# RC_motor_driver.net
KiCad netlist of a schematic drawn in Altium Designer
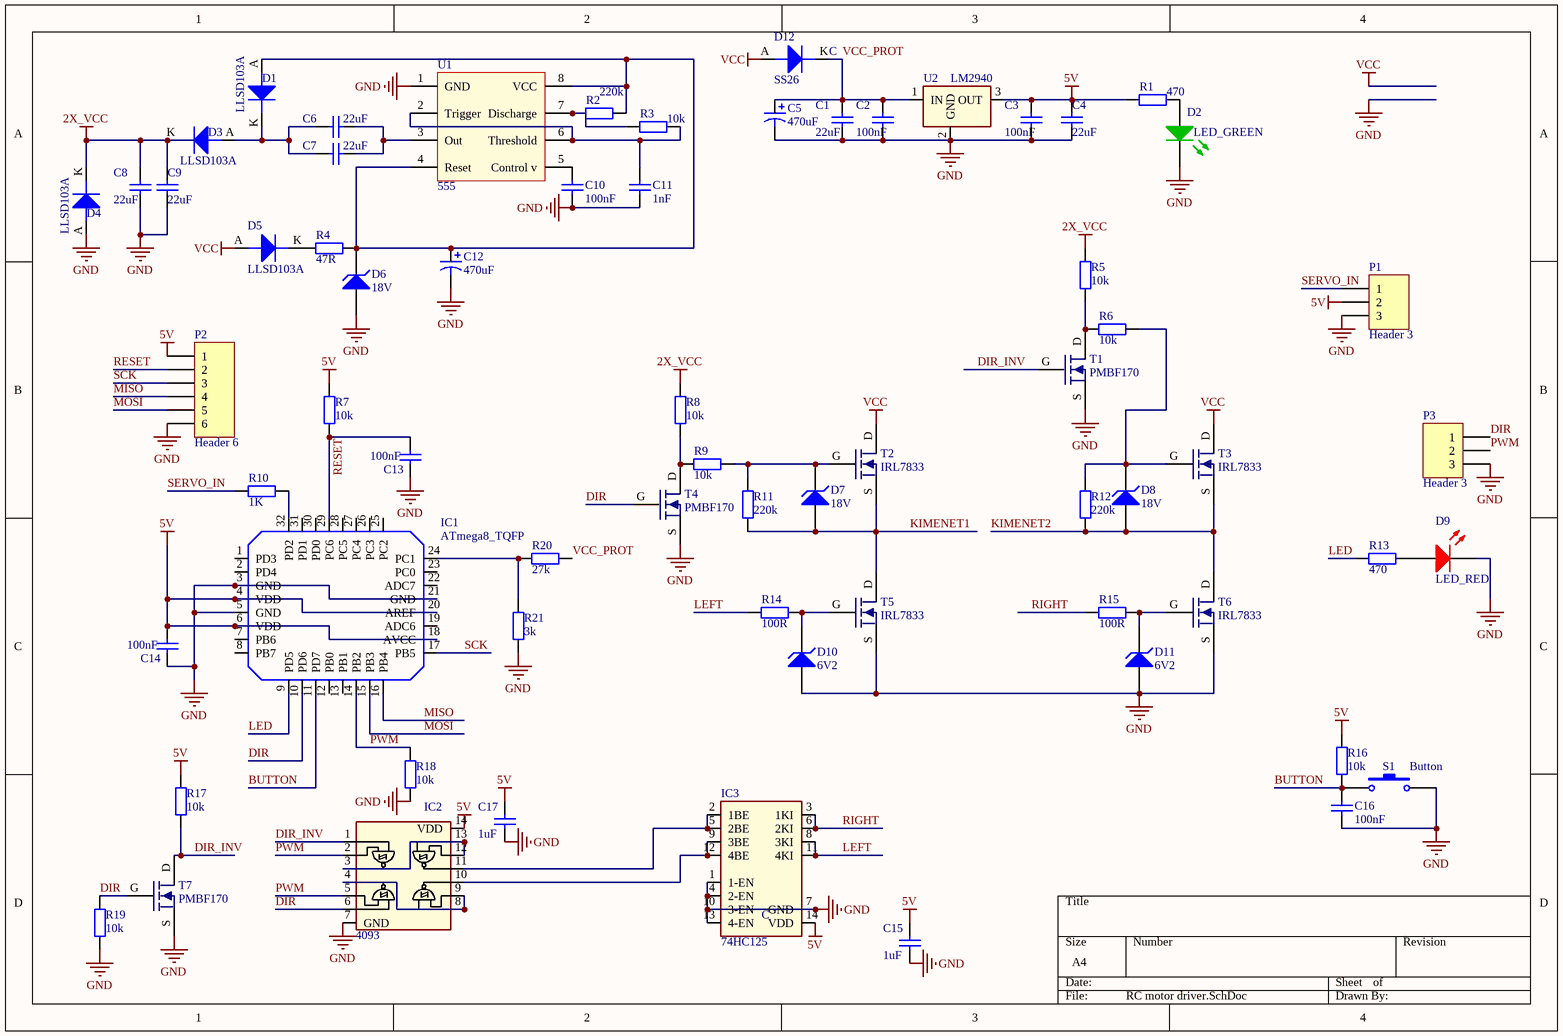
[diagram p0: RC motor driver.SchDoc]

(export (version "E")
  (design (tool "Eeschema 10.0.6"))
  (components
    (comp (ref "C1")
      (value "22uF")
      (footprint "FP_1210_CAP_N")
      (description "Capacitor")
      (libsource (lib "Capacitor") (part "CAP"))
    )
    (comp (ref "C2")
      (value "100nF")
      (footprint "FP_0805_CAP_085")
      (description "Capacitor")
      (libsource (lib "Capacitor") (part "CAP"))
    )
    (comp (ref "C3")
      (value "100nF")
      (footprint "FP_0805_CAP_085")
      (description "Capacitor")
      (libsource (lib "Capacitor") (part "CAP"))
    )
    (comp (ref "C4")
      (value "22uF")
      (footprint "FP_1210_CAP_N")
      (description "Capacitor")
      (libsource (lib "Capacitor") (part "CAP"))
    )
    (comp (ref "C5")
      (value "470uF")
      (footprint "cap_10x12")
      (description "Polarized Capacitor")
      (libsource (lib "Capacitor") (part "CAP_ELECT"))
    )
    (comp (ref "C6")
      (value "22uF")
      (footprint "FP_1210_CAP_N")
      (description "Capacitor")
      (libsource (lib "Capacitor") (part "CAP"))
    )
    (comp (ref "C7")
      (value "22uF")
      (footprint "FP_1210_CAP_N")
      (description "Capacitor")
      (libsource (lib "Capacitor") (part "CAP"))
    )
    (comp (ref "C8")
      (value "22uF")
      (footprint "FP_1210_CAP_N")
      (description "Capacitor")
      (libsource (lib "Capacitor") (part "CAP"))
    )
    (comp (ref "C9")
      (value "22uF")
      (footprint "FP_1210_CAP_N")
      (description "Capacitor")
      (libsource (lib "Capacitor") (part "CAP"))
    )
    (comp (ref "C10")
      (value "100nF")
      (footprint "FP_0805_CAP_085")
      (description "Capacitor")
      (libsource (lib "Capacitor") (part "CAP"))
    )
    (comp (ref "C11")
      (value "1nF")
      (footprint "FP_0805_CAP_085")
      (description "Capacitor")
      (libsource (lib "Capacitor") (part "CAP"))
    )
    (comp (ref "C12")
      (value "470uF")
      (footprint "cap_10x12")
      (description "Polarized Capacitor")
      (libsource (lib "Capacitor") (part "CAP_ELECT"))
    )
    (comp (ref "C13")
      (value "100nF")
      (footprint "FP_0805_CAP_085")
      (description "Capacitor")
      (libsource (lib "Capacitor") (part "CAP"))
    )
    (comp (ref "C14")
      (value "100nF")
      (footprint "FP_0805_CAP_085")
      (description "Capacitor")
      (libsource (lib "Capacitor") (part "CAP"))
    )
    (comp (ref "C15")
      (value "1uF")
      (footprint "FP_0805_CAP_085")
      (description "Capacitor")
      (libsource (lib "Capacitor") (part "CAP"))
    )
    (comp (ref "C16")
      (value "100nF")
      (footprint "FP_0805_CAP_085")
      (description "Capacitor")
      (libsource (lib "Capacitor") (part "CAP"))
    )
    (comp (ref "C17")
      (value "1uF")
      (footprint "FP_0805_CAP_085")
      (description "Capacitor")
      (libsource (lib "Capacitor") (part "CAP"))
    )
    (comp (ref "D1") (value "LLSD103A") (footprint "SOD-80") (libsource (lib "Diode") (part "DIODE_big")))
    (comp (ref "D2")
      (value "LED_GREEN")
      (footprint "FP_0805_LED_GREEN")
      (description "Typical LED")
      (libsource (lib "Led_optical") (part "LED_G"))
    )
    (comp (ref "D3") (value "LLSD103A") (footprint "SOD-80") (libsource (lib "Diode") (part "DIODE_big")))
    (comp (ref "D4") (value "LLSD103A") (footprint "SOD-80") (libsource (lib "Diode") (part "DIODE_big")))
    (comp (ref "D5") (value "LLSD103A") (footprint "SOD-80") (libsource (lib "Diode") (part "DIODE_big")))
    (comp (ref "D6")
      (value "18V")
      (footprint "SOD-80")
      (description "Zener Diode")
      (libsource (lib "Diode") (part "ZENER"))
    )
    (comp (ref "D7")
      (value "18V")
      (footprint "SOD-80")
      (description "Zener Diode")
      (libsource (lib "Diode") (part "ZENER"))
    )
    (comp (ref "D8")
      (value "18V")
      (footprint "SOD-80")
      (description "Zener Diode")
      (libsource (lib "Diode") (part "ZENER"))
    )
    (comp (ref "D9")
      (value "LED_RED")
      (footprint "FP_0805_LED_RED")
      (description "Typical LED")
      (libsource (lib "Led_optical") (part "LED_R"))
    )
    (comp (ref "D10")
      (value "6V2")
      (footprint "SOD-80")
      (description "Zener Diode")
      (libsource (lib "Diode") (part "ZENER"))
    )
    (comp (ref "D11")
      (value "6V2")
      (footprint "SOD-80")
      (description "Zener Diode")
      (libsource (lib "Diode") (part "ZENER"))
    )
    (comp (ref "D12") (value "SS26") (footprint "subsma") (libsource (lib "Diode") (part "DIODE_big")))
    (comp (ref "IC1")
      (value "ATmega8_TQFP")
      (footprint "TQFP32_N")
      (libsource (lib "uC") (part "ATmega8_TQFP"))
    )
    (comp (ref "IC2")
      (value "4093")
      (footprint "Gate_SOIC14")
      (description "Quad 2-Input NAND Schmitt Trigger")
      (libsource (lib "Logic_gate") (part "4093"))
    )
    (comp (ref "IC3")
      (value "74HC125")
      (footprint "Gate_SOIC14")
      (libsource (lib "Logic_gate") (part "74HC125"))
    )
    (comp (ref "P1")
      (value "Header 3")
      (footprint "HDR1X3")
      (description "Header, 3-Pin")
      (fields (field (name "PUBLISHER") "Altium Limited"))
      (libsource (lib "Miscellaneous Connectors") (part "Header 3"))
    )
    (comp (ref "P2")
      (value "Header 6")
      (footprint "HDR1X6")
      (description "Header, 6-Pin")
      (fields (field (name "PUBLISHER") "Altium Limited"))
      (libsource (lib "Miscellaneous Connectors") (part "Header 6"))
    )
    (comp (ref "P3")
      (value "Header 3")
      (footprint "HDR1X3")
      (description "Header, 3-Pin")
      (fields (field (name "PUBLISHER") "Altium Limited"))
      (libsource (lib "") (part "Header 3_1"))
    )
    (comp (ref "R1")
      (value "470")
      (footprint "FP_0805_RES")
      (description "Resistor")
      (libsource (lib "") (part "RES_1"))
    )
    (comp (ref "R2")
      (value "220k")
      (footprint "FP_0805_RES")
      (description "Resistor")
      (libsource (lib "") (part "RES_1"))
    )
    (comp (ref "R3")
      (value "10k")
      (footprint "FP_0805_RES")
      (description "Resistor")
      (libsource (lib "") (part "RES_1"))
    )
    (comp (ref "R4")
      (value "47R")
      (footprint "FP_0805_RES")
      (description "Resistor")
      (libsource (lib "") (part "RES_1"))
    )
    (comp (ref "R5")
      (value "10k")
      (footprint "FP_0805_RES")
      (description "Resistor")
      (libsource (lib "Resistor") (part "RES"))
    )
    (comp (ref "R6")
      (value "10k")
      (footprint "FP_0805_RES")
      (description "Resistor")
      (libsource (lib "") (part "RES_1"))
    )
    (comp (ref "R7")
      (value "10k")
      (footprint "FP_0805_RES")
      (description "Resistor")
      (libsource (lib "Resistor") (part "RES"))
    )
    (comp (ref "R8")
      (value "10k")
      (footprint "FP_0805_RES")
      (description "Resistor")
      (libsource (lib "Resistor") (part "RES"))
    )
    (comp (ref "R9")
      (value "10k")
      (footprint "FP_0805_RES")
      (description "Resistor")
      (libsource (lib "") (part "RES_1"))
    )
    (comp (ref "R10")
      (value "1K")
      (footprint "FP_0805_RES")
      (description "Resistor")
      (libsource (lib "") (part "RES_2"))
    )
    (comp (ref "R11")
      (value "220k")
      (footprint "FP_0805_RES")
      (description "Resistor")
      (libsource (lib "Resistor") (part "RES"))
    )
    (comp (ref "R12")
      (value "220k")
      (footprint "FP_0805_RES")
      (description "Resistor")
      (libsource (lib "Resistor") (part "RES"))
    )
    (comp (ref "R13")
      (value "470")
      (footprint "FP_0805_RES")
      (description "Resistor")
      (libsource (lib "") (part "RES_1"))
    )
    (comp (ref "R14")
      (value "100R")
      (footprint "FP_0805_RES")
      (description "Resistor")
      (libsource (lib "") (part "RES_1"))
    )
    (comp (ref "R15")
      (value "100R")
      (footprint "FP_0805_RES")
      (description "Resistor")
      (libsource (lib "") (part "RES_1"))
    )
    (comp (ref "R16")
      (value "10k")
      (footprint "FP_0805_RES")
      (description "Resistor")
      (libsource (lib "Resistor") (part "RES"))
    )
    (comp (ref "R17")
      (value "10k")
      (footprint "FP_0805_RES")
      (description "Resistor")
      (libsource (lib "Resistor") (part "RES"))
    )
    (comp (ref "R18")
      (value "10k")
      (footprint "FP_0805_RES")
      (description "Resistor")
      (libsource (lib "Resistor") (part "RES"))
    )
    (comp (ref "R19")
      (value "10k")
      (footprint "FP_0805_RES")
      (description "Resistor")
      (libsource (lib "Resistor") (part "RES"))
    )
    (comp (ref "R20")
      (value "27k")
      (footprint "FP_0805_RES")
      (description "Resistor")
      (libsource (lib "") (part "RES_2"))
    )
    (comp (ref "R21")
      (value "3k")
      (footprint "FP_0805_RES")
      (description "Resistor")
      (libsource (lib "Resistor") (part "RES"))
    )
    (comp (ref "S1")
      (value "Button")
      (footprint "BUTTON_6X6 _SMD")
      (description "Switch")
      (fields (field (name "PUBLISHER") "Altium Limited"))
      (libsource (lib "Miscellaneous Devices") (part "SW-PB"))
    )
    (comp (ref "T1") (value "PMBF170") (footprint "FET_SOT23") (libsource (lib "FET") (part "NMOS")))
    (comp (ref "T2")
      (value "IRL7833")
      (footprint "FET_TO220-3 bent legs - inverse")
      (libsource (lib "FET") (part "NMOS"))
    )
    (comp (ref "T3")
      (value "IRL7833")
      (footprint "FET_TO220-3 bent legs - inverse")
      (libsource (lib "FET") (part "NMOS"))
    )
    (comp (ref "T4") (value "PMBF170") (footprint "FET_SOT23") (libsource (lib "FET") (part "NMOS")))
    (comp (ref "T5")
      (value "IRL7833")
      (footprint "FET_TO220-3 bent legs - inverse")
      (libsource (lib "FET") (part "NMOS"))
    )
    (comp (ref "T6")
      (value "IRL7833")
      (footprint "FET_TO220-3 bent legs - inverse")
      (libsource (lib "FET") (part "NMOS"))
    )
    (comp (ref "T7") (value "PMBF170") (footprint "FET_SOT23") (libsource (lib "FET") (part "NMOS")))
    (comp (ref "U1")
      (value "555")
      (footprint "DIGITAL_SOIC8")
      (description "555 Counter")
      (libsource (lib "Digital") (part "555"))
    )
    (comp (ref "U2")
      (value "LM2940")
      (footprint "SUPPLY_TO220-3 bent legs - inverse")
      (libsource (lib "Supply") (part "78xx"))
    )
  )
  (nets
    (net (code "1") (name "/BUTTON") (class "Default")
      (node (ref "C16") (pin "2") (pinfunction "2_2") (pintype "passive"))
      (node (ref "IC1") (pin "11") (pinfunction "PD7_11") (pintype "passive"))
      (node (ref "R16") (pin "1") (pinfunction "1_1") (pintype "passive"))
      (node (ref "S1") (pin "1") (pinfunction "1_1") (pintype "passive"))
    )
    (net (code "2") (name "/DIR") (class "Default")
      (node (ref "IC1") (pin "10") (pinfunction "PD6_10") (pintype "passive"))
      (node (ref "IC2") (pin "6") (pintype "passive"))
      (node (ref "P3") (pin "1") (pinfunction "1_1") (pintype "passive"))
      (node (ref "R19") (pin "2") (pinfunction "2_2") (pintype "passive"))
      (node (ref "T4") (pin "G") (pinfunction "G_G") (pintype "passive"))
      (node (ref "T7") (pin "G") (pinfunction "G_G") (pintype "passive"))
    )
    (net (code "3") (name "/DIR_INV") (class "Default")
      (node (ref "IC2") (pin "1") (pintype "passive"))
      (node (ref "R17") (pin "1") (pinfunction "1_1") (pintype "passive"))
      (node (ref "T1") (pin "G") (pinfunction "G_G") (pintype "passive"))
      (node (ref "T7") (pin "D") (pinfunction "D_D") (pintype "passive"))
    )
    (net (code "4") (name "/KIMENET1") (class "Default")
      (node (ref "D7") (pin "A") (pinfunction "A_A") (pintype "passive"))
      (node (ref "R11") (pin "1") (pinfunction "1_1") (pintype "passive"))
      (node (ref "T2") (pin "S") (pinfunction "S_S") (pintype "passive"))
      (node (ref "T5") (pin "D") (pinfunction "D_D") (pintype "passive"))
    )
    (net (code "5") (name "/KIMENET2") (class "Default")
      (node (ref "D8") (pin "A") (pinfunction "A_A") (pintype "passive"))
      (node (ref "R12") (pin "1") (pinfunction "1_1") (pintype "passive"))
      (node (ref "T3") (pin "S") (pinfunction "S_S") (pintype "passive"))
      (node (ref "T6") (pin "D") (pinfunction "D_D") (pintype "passive"))
    )
    (net (code "6") (name "/LED") (class "Default")
      (node (ref "IC1") (pin "9") (pinfunction "PD5_9") (pintype "passive"))
      (node (ref "R13") (pin "1") (pinfunction "1_1") (pintype "passive"))
    )
    (net (code "7") (name "/LEFT") (class "Default")
      (node (ref "IC3") (pin "11") (pinfunction "4KI_11") (pintype "passive"))
      (node (ref "IC3") (pin "8") (pinfunction "3KI_8") (pintype "passive"))
      (node (ref "R14") (pin "1") (pinfunction "1_1") (pintype "passive"))
    )
    (net (code "8") (name "/MISO") (class "Default")
      (node (ref "IC1") (pin "16") (pinfunction "PB4_16") (pintype "passive"))
      (node (ref "P2") (pin "4") (pinfunction "4_4") (pintype "passive"))
    )
    (net (code "9") (name "/MOSI") (class "Default")
      (node (ref "IC1") (pin "15") (pinfunction "PB3_15") (pintype "passive"))
      (node (ref "P2") (pin "5") (pinfunction "5_5") (pintype "passive"))
    )
    (net (code "10") (name "/PWM") (class "Default")
      (node (ref "IC1") (pin "14") (pinfunction "PB2_14") (pintype "passive"))
      (node (ref "IC2") (pin "2") (pintype "passive"))
      (node (ref "IC2") (pin "5") (pintype "passive"))
      (node (ref "P3") (pin "2") (pinfunction "2_2") (pintype "passive"))
      (node (ref "R18") (pin "2") (pinfunction "2_2") (pintype "passive"))
    )
    (net (code "11") (name "/RESET") (class "Default")
      (node (ref "C13") (pin "2") (pinfunction "2_2") (pintype "passive"))
      (node (ref "IC1") (pin "29") (pinfunction "PC6_29") (pintype "passive"))
      (node (ref "P2") (pin "2") (pinfunction "2_2") (pintype "passive"))
      (node (ref "R7") (pin "1") (pinfunction "1_1") (pintype "passive"))
    )
    (net (code "12") (name "/RIGHT") (class "Default")
      (node (ref "IC3") (pin "3") (pinfunction "1KI_3") (pintype "passive"))
      (node (ref "IC3") (pin "6") (pinfunction "2KI_6") (pintype "passive"))
      (node (ref "R15") (pin "1") (pinfunction "1_1") (pintype "passive"))
    )
    (net (code "13") (name "/SCK") (class "Default")
      (node (ref "IC1") (pin "17") (pinfunction "PB5_17") (pintype "passive"))
      (node (ref "P2") (pin "3") (pinfunction "3_3") (pintype "passive"))
    )
    (net (code "14") (name "/SERVO_IN") (class "Default")
      (node (ref "P1") (pin "1") (pinfunction "1_1") (pintype "passive"))
      (node (ref "R10") (pin "2") (pinfunction "2_2") (pintype "passive"))
    )
    (net (code "15") (name "/VCC_PROT") (class "Default")
      (node (ref "C1") (pin "1") (pinfunction "1_1") (pintype "passive"))
      (node (ref "C2") (pin "1") (pinfunction "1_1") (pintype "passive"))
      (node (ref "C5") (pin "P") (pintype "passive"))
      (node (ref "D12") (pin "K") (pinfunction "K_K") (pintype "passive"))
      (node (ref "R20") (pin "1") (pinfunction "1_1") (pintype "passive"))
      (node (ref "U2") (pin "1") (pinfunction "IN_1") (pintype "power_in"))
    )
    (net (code "16") (name "2X_VCC") (class "Default")
      (node (ref "C8") (pin "1") (pinfunction "1_1") (pintype "passive"))
      (node (ref "C9") (pin "1") (pinfunction "1_1") (pintype "passive"))
      (node (ref "D3") (pin "K") (pinfunction "K_K") (pintype "passive"))
      (node (ref "D4") (pin "K") (pinfunction "K_K") (pintype "passive"))
      (node (ref "R5") (pin "2") (pinfunction "2_2") (pintype "passive"))
      (node (ref "R8") (pin "2") (pinfunction "2_2") (pintype "passive"))
    )
    (net (code "17") (name "5V") (class "Default")
      (node (ref "C14") (pin "2") (pinfunction "2_2") (pintype "passive"))
      (node (ref "C15") (pin "1") (pinfunction "1_1") (pintype "passive"))
      (node (ref "C17") (pin "1") (pinfunction "1_1") (pintype "passive"))
      (node (ref "C3") (pin "1") (pinfunction "1_1") (pintype "passive"))
      (node (ref "C4") (pin "1") (pinfunction "1_1") (pintype "passive"))
      (node (ref "IC1") (pin "18") (pinfunction "AVCC_18") (pintype "passive"))
      (node (ref "IC1") (pin "20") (pinfunction "AREF_20") (pintype "passive"))
      (node (ref "IC1") (pin "4") (pinfunction "VDD_4") (pintype "passive"))
      (node (ref "IC1") (pin "6") (pinfunction "VDD_6") (pintype "passive"))
      (node (ref "IC2") (pin "14") (pinfunction "VDD_14") (pintype "passive"))
      (node (ref "IC3") (pin "14") (pinfunction "VDD_14") (pintype "passive"))
      (node (ref "P1") (pin "2") (pinfunction "2_2") (pintype "passive"))
      (node (ref "P2") (pin "1") (pinfunction "1_1") (pintype "passive"))
      (node (ref "R1") (pin "1") (pinfunction "1_1") (pintype "passive"))
      (node (ref "R16") (pin "2") (pinfunction "2_2") (pintype "passive"))
      (node (ref "R17") (pin "2") (pinfunction "2_2") (pintype "passive"))
      (node (ref "R7") (pin "2") (pinfunction "2_2") (pintype "passive"))
      (node (ref "U2") (pin "3") (pinfunction "OUT_3") (pintype "power_in"))
    )
    (net (code "18") (name "GND") (class "Default")
      (node (ref "C1") (pin "2") (pinfunction "2_2") (pintype "passive"))
      (node (ref "C10") (pin "2") (pinfunction "2_2") (pintype "passive"))
      (node (ref "C11") (pin "2") (pinfunction "2_2") (pintype "passive"))
      (node (ref "C12") (pin "N") (pintype "passive"))
      (node (ref "C13") (pin "1") (pinfunction "1_1") (pintype "passive"))
      (node (ref "C14") (pin "1") (pinfunction "1_1") (pintype "passive"))
      (node (ref "C15") (pin "2") (pinfunction "2_2") (pintype "passive"))
      (node (ref "C16") (pin "1") (pinfunction "1_1") (pintype "passive"))
      (node (ref "C17") (pin "2") (pinfunction "2_2") (pintype "passive"))
      (node (ref "C2") (pin "2") (pinfunction "2_2") (pintype "passive"))
      (node (ref "C3") (pin "2") (pinfunction "2_2") (pintype "passive"))
      (node (ref "C4") (pin "2") (pinfunction "2_2") (pintype "passive"))
      (node (ref "C5") (pin "N") (pintype "passive"))
      (node (ref "C8") (pin "2") (pinfunction "2_2") (pintype "passive"))
      (node (ref "C9") (pin "2") (pinfunction "2_2") (pintype "passive"))
      (node (ref "D10") (pin "A") (pinfunction "A_A") (pintype "passive"))
      (node (ref "D11") (pin "A") (pinfunction "A_A") (pintype "passive"))
      (node (ref "D2") (pin "K") (pinfunction "K_K") (pintype "passive"))
      (node (ref "D4") (pin "A") (pinfunction "A_A") (pintype "passive"))
      (node (ref "D6") (pin "A") (pinfunction "A_A") (pintype "passive"))
      (node (ref "D9") (pin "K") (pinfunction "K_K") (pintype "passive"))
      (node (ref "IC1") (pin "21") (pinfunction "GND_21") (pintype "passive"))
      (node (ref "IC1") (pin "3") (pinfunction "GND_3") (pintype "passive"))
      (node (ref "IC1") (pin "5") (pinfunction "GND_5") (pintype "passive"))
      (node (ref "IC2") (pin "7") (pinfunction "GND_7") (pintype "passive"))
      (node (ref "IC3") (pin "1") (pinfunction "1-EN_1") (pintype "passive"))
      (node (ref "IC3") (pin "10") (pinfunction "3-EN_10") (pintype "passive"))
      (node (ref "IC3") (pin "13") (pinfunction "4-EN_13") (pintype "passive"))
      (node (ref "IC3") (pin "4") (pinfunction "2-EN_4") (pintype "passive"))
      (node (ref "IC3") (pin "7") (pinfunction "GND_7") (pintype "passive"))
      (node (ref "P1") (pin "3") (pinfunction "3_3") (pintype "passive"))
      (node (ref "P2") (pin "6") (pinfunction "6_6") (pintype "passive"))
      (node (ref "P3") (pin "3") (pinfunction "3_3") (pintype "passive"))
      (node (ref "R18") (pin "1") (pinfunction "1_1") (pintype "passive"))
      (node (ref "R19") (pin "1") (pinfunction "1_1") (pintype "passive"))
      (node (ref "R21") (pin "1") (pinfunction "1_1") (pintype "passive"))
      (node (ref "S1") (pin "2") (pinfunction "2_2") (pintype "passive"))
      (node (ref "T1") (pin "S") (pinfunction "S_S") (pintype "passive"))
      (node (ref "T4") (pin "S") (pinfunction "S_S") (pintype "passive"))
      (node (ref "T5") (pin "S") (pinfunction "S_S") (pintype "passive"))
      (node (ref "T6") (pin "S") (pinfunction "S_S") (pintype "passive"))
      (node (ref "T7") (pin "S") (pinfunction "S_S") (pintype "passive"))
      (node (ref "U1") (pin "1") (pinfunction "GND_1") (pintype "passive"))
      (node (ref "U2") (pin "2") (pinfunction "GND_2") (pintype "power_in"))
    )
    (net (code "19") (name "Net-(C6-Pad2)") (class "Default")
      (node (ref "C6") (pin "2") (pinfunction "2_2") (pintype "passive"))
      (node (ref "C7") (pin "2") (pinfunction "2_2") (pintype "passive"))
      (node (ref "D1") (pin "K") (pinfunction "K_K") (pintype "passive"))
      (node (ref "D3") (pin "A") (pinfunction "A_A") (pintype "passive"))
    )
    (net (code "20") (name "Net-(D2-PadA)") (class "Default")
      (node (ref "D2") (pin "A") (pinfunction "A_A") (pintype "passive"))
      (node (ref "R1") (pin "2") (pinfunction "2_2") (pintype "passive"))
    )
    (net (code "21") (name "Net-(D5-PadK)") (class "Default")
      (node (ref "D5") (pin "K") (pinfunction "K_K") (pintype "passive"))
      (node (ref "R4") (pin "1") (pinfunction "1_1") (pintype "passive"))
    )
    (net (code "22") (name "Net-(D7-PadK)") (class "Default")
      (node (ref "D7") (pin "K") (pinfunction "K_K") (pintype "passive"))
      (node (ref "R11") (pin "2") (pinfunction "2_2") (pintype "passive"))
      (node (ref "R9") (pin "2") (pinfunction "2_2") (pintype "passive"))
      (node (ref "T2") (pin "G") (pinfunction "G_G") (pintype "passive"))
    )
    (net (code "23") (name "Net-(D8-PadK)") (class "Default")
      (node (ref "D8") (pin "K") (pinfunction "K_K") (pintype "passive"))
      (node (ref "R12") (pin "2") (pinfunction "2_2") (pintype "passive"))
      (node (ref "R6") (pin "2") (pinfunction "2_2") (pintype "passive"))
      (node (ref "T3") (pin "G") (pinfunction "G_G") (pintype "passive"))
    )
    (net (code "24") (name "Net-(D9-PadA)") (class "Default")
      (node (ref "D9") (pin "A") (pinfunction "A_A") (pintype "passive"))
      (node (ref "R13") (pin "2") (pinfunction "2_2") (pintype "passive"))
    )
    (net (code "25") (name "Net-(D10-PadK)") (class "Default")
      (node (ref "D10") (pin "K") (pinfunction "K_K") (pintype "passive"))
      (node (ref "R14") (pin "2") (pinfunction "2_2") (pintype "passive"))
      (node (ref "T5") (pin "G") (pinfunction "G_G") (pintype "passive"))
    )
    (net (code "26") (name "Net-(D11-PadK)") (class "Default")
      (node (ref "D11") (pin "K") (pinfunction "K_K") (pintype "passive"))
      (node (ref "R15") (pin "2") (pinfunction "2_2") (pintype "passive"))
      (node (ref "T6") (pin "G") (pinfunction "G_G") (pintype "passive"))
    )
    (net (code "27") (name "Net-(IC1-PC1)") (class "Default")
      (node (ref "IC1") (pin "24") (pinfunction "PC1_24") (pintype "passive"))
      (node (ref "R20") (pin "2") (pinfunction "2_2") (pintype "passive"))
      (node (ref "R21") (pin "2") (pinfunction "2_2") (pintype "passive"))
    )
    (net (code "28") (name "Net-(IC1-PD2)") (class "Default")
      (node (ref "IC1") (pin "32") (pinfunction "PD2_32") (pintype "passive"))
      (node (ref "R10") (pin "1") (pinfunction "1_1") (pintype "passive"))
    )
    (net (code "29") (name "Net-(IC2-Pad4)") (class "Default")
      (node (ref "IC2") (pin "4") (pintype "passive"))
      (node (ref "IC2") (pin "8") (pintype "passive"))
      (node (ref "IC2") (pin "9") (pintype "passive"))
    )
    (net (code "30") (name "Net-(IC2-Pad12)") (class "Default")
      (node (ref "IC2") (pin "12") (pintype "passive"))
      (node (ref "IC2") (pin "13") (pintype "passive"))
      (node (ref "IC2") (pin "3") (pintype "passive"))
    )
    (net (code "31") (name "Net-(IC3-1BE)") (class "Default")
      (node (ref "IC2") (pin "11") (pintype "passive"))
      (node (ref "IC3") (pin "2") (pinfunction "1BE_2") (pintype "passive"))
      (node (ref "IC3") (pin "5") (pinfunction "2BE_5") (pintype "passive"))
    )
    (net (code "32") (name "Net-(IC3-3BE)") (class "Default")
      (node (ref "IC2") (pin "10") (pintype "passive"))
      (node (ref "IC3") (pin "12") (pinfunction "4BE_12") (pintype "passive"))
      (node (ref "IC3") (pin "9") (pinfunction "3BE_9") (pintype "passive"))
    )
    (net (code "33") (name "Net-(R5-Pad1)") (class "Default")
      (node (ref "R5") (pin "1") (pinfunction "1_1") (pintype "passive"))
      (node (ref "R6") (pin "1") (pinfunction "1_1") (pintype "passive"))
      (node (ref "T1") (pin "D") (pinfunction "D_D") (pintype "passive"))
    )
    (net (code "34") (name "Net-(R8-Pad1)") (class "Default")
      (node (ref "R8") (pin "1") (pinfunction "1_1") (pintype "passive"))
      (node (ref "R9") (pin "1") (pinfunction "1_1") (pintype "passive"))
      (node (ref "T4") (pin "D") (pinfunction "D_D") (pintype "passive"))
    )
    (net (code "35") (name "Net-(U1-Control_v)") (class "Default")
      (node (ref "C10") (pin "1") (pinfunction "1_1") (pintype "passive"))
      (node (ref "U1") (pin "5") (pinfunction "Control_v_5") (pintype "passive"))
    )
    (net (code "36") (name "Net-(U1-Discharge)") (class "Default")
      (node (ref "R2") (pin "1") (pinfunction "1_1") (pintype "passive"))
      (node (ref "R3") (pin "1") (pinfunction "1_1") (pintype "passive"))
      (node (ref "U1") (pin "7") (pinfunction "Discharge_7") (pintype "passive"))
    )
    (net (code "37") (name "Net-(U1-Out)") (class "Default")
      (node (ref "C6") (pin "1") (pinfunction "1_1") (pintype "passive"))
      (node (ref "C7") (pin "1") (pinfunction "1_1") (pintype "passive"))
      (node (ref "U1") (pin "3") (pinfunction "Out_3") (pintype "passive"))
    )
    (net (code "38") (name "Net-(U1-Reset)") (class "Default")
      (node (ref "C12") (pin "P") (pintype "passive"))
      (node (ref "D1") (pin "A") (pinfunction "A_A") (pintype "passive"))
      (node (ref "D6") (pin "K") (pinfunction "K_K") (pintype "passive"))
      (node (ref "R2") (pin "2") (pinfunction "2_2") (pintype "passive"))
      (node (ref "R4") (pin "2") (pinfunction "2_2") (pintype "passive"))
      (node (ref "U1") (pin "4") (pinfunction "Reset_4") (pintype "passive"))
      (node (ref "U1") (pin "8") (pinfunction "VCC_8") (pintype "passive"))
    )
    (net (code "39") (name "Net-(U1-Threshold)") (class "Default")
      (node (ref "C11") (pin "1") (pinfunction "1_1") (pintype "passive"))
      (node (ref "R3") (pin "2") (pinfunction "2_2") (pintype "passive"))
      (node (ref "U1") (pin "2") (pinfunction "Trigger_2") (pintype "passive"))
      (node (ref "U1") (pin "6") (pinfunction "Threshold_6") (pintype "passive"))
    )
    (net (code "40") (name "VCC") (class "Default")
      (node (ref "D12") (pin "A") (pinfunction "A_A") (pintype "passive"))
      (node (ref "D5") (pin "A") (pinfunction "A_A") (pintype "passive"))
      (node (ref "T2") (pin "D") (pinfunction "D_D") (pintype "passive"))
      (node (ref "T3") (pin "D") (pinfunction "D_D") (pintype "passive"))
    )
    (net (code "41") (name "unconnected-(IC1-ADC6-Pad19)") (class "Default")
      (node (ref "IC1") (pin "19") (pinfunction "ADC6_19") (pintype "passive"))
    )
    (net (code "42") (name "unconnected-(IC1-ADC7-Pad22)") (class "Default")
      (node (ref "IC1") (pin "22") (pinfunction "ADC7_22") (pintype "passive"))
    )
    (net (code "43") (name "unconnected-(IC1-PB0-Pad12)") (class "Default")
      (node (ref "IC1") (pin "12") (pinfunction "PB0_12") (pintype "passive"))
    )
    (net (code "44") (name "unconnected-(IC1-PB1-Pad13)") (class "Default")
      (node (ref "IC1") (pin "13") (pinfunction "PB1_13") (pintype "passive"))
    )
    (net (code "45") (name "unconnected-(IC1-PB6-Pad7)") (class "Default")
      (node (ref "IC1") (pin "7") (pinfunction "PB6_7") (pintype "passive"))
    )
    (net (code "46") (name "unconnected-(IC1-PB7-Pad8)") (class "Default")
      (node (ref "IC1") (pin "8") (pinfunction "PB7_8") (pintype "passive"))
    )
    (net (code "47") (name "unconnected-(IC1-PC0-Pad23)") (class "Default")
      (node (ref "IC1") (pin "23") (pinfunction "PC0_23") (pintype "passive"))
    )
    (net (code "48") (name "unconnected-(IC1-PC2-Pad25)") (class "Default")
      (node (ref "IC1") (pin "25") (pinfunction "PC2_25") (pintype "passive"))
    )
    (net (code "49") (name "unconnected-(IC1-PC3-Pad26)") (class "Default")
      (node (ref "IC1") (pin "26") (pinfunction "PC3_26") (pintype "passive"))
    )
    (net (code "50") (name "unconnected-(IC1-PC4-Pad27)") (class "Default")
      (node (ref "IC1") (pin "27") (pinfunction "PC4_27") (pintype "passive"))
    )
    (net (code "51") (name "unconnected-(IC1-PC5-Pad28)") (class "Default")
      (node (ref "IC1") (pin "28") (pinfunction "PC5_28") (pintype "passive"))
    )
    (net (code "52") (name "unconnected-(IC1-PD0-Pad30)") (class "Default")
      (node (ref "IC1") (pin "30") (pinfunction "PD0_30") (pintype "passive"))
    )
    (net (code "53") (name "unconnected-(IC1-PD1-Pad31)") (class "Default")
      (node (ref "IC1") (pin "31") (pinfunction "PD1_31") (pintype "passive"))
    )
    (net (code "54") (name "unconnected-(IC1-PD3-Pad1)") (class "Default")
      (node (ref "IC1") (pin "1") (pinfunction "PD3_1") (pintype "passive"))
    )
    (net (code "55") (name "unconnected-(IC1-PD4-Pad2)") (class "Default")
      (node (ref "IC1") (pin "2") (pinfunction "PD4_2") (pintype "passive"))
    )
  )
)
